# FOTA_LED_Indicators.net
KiCad netlist of a schematic drawn in Altium Designer
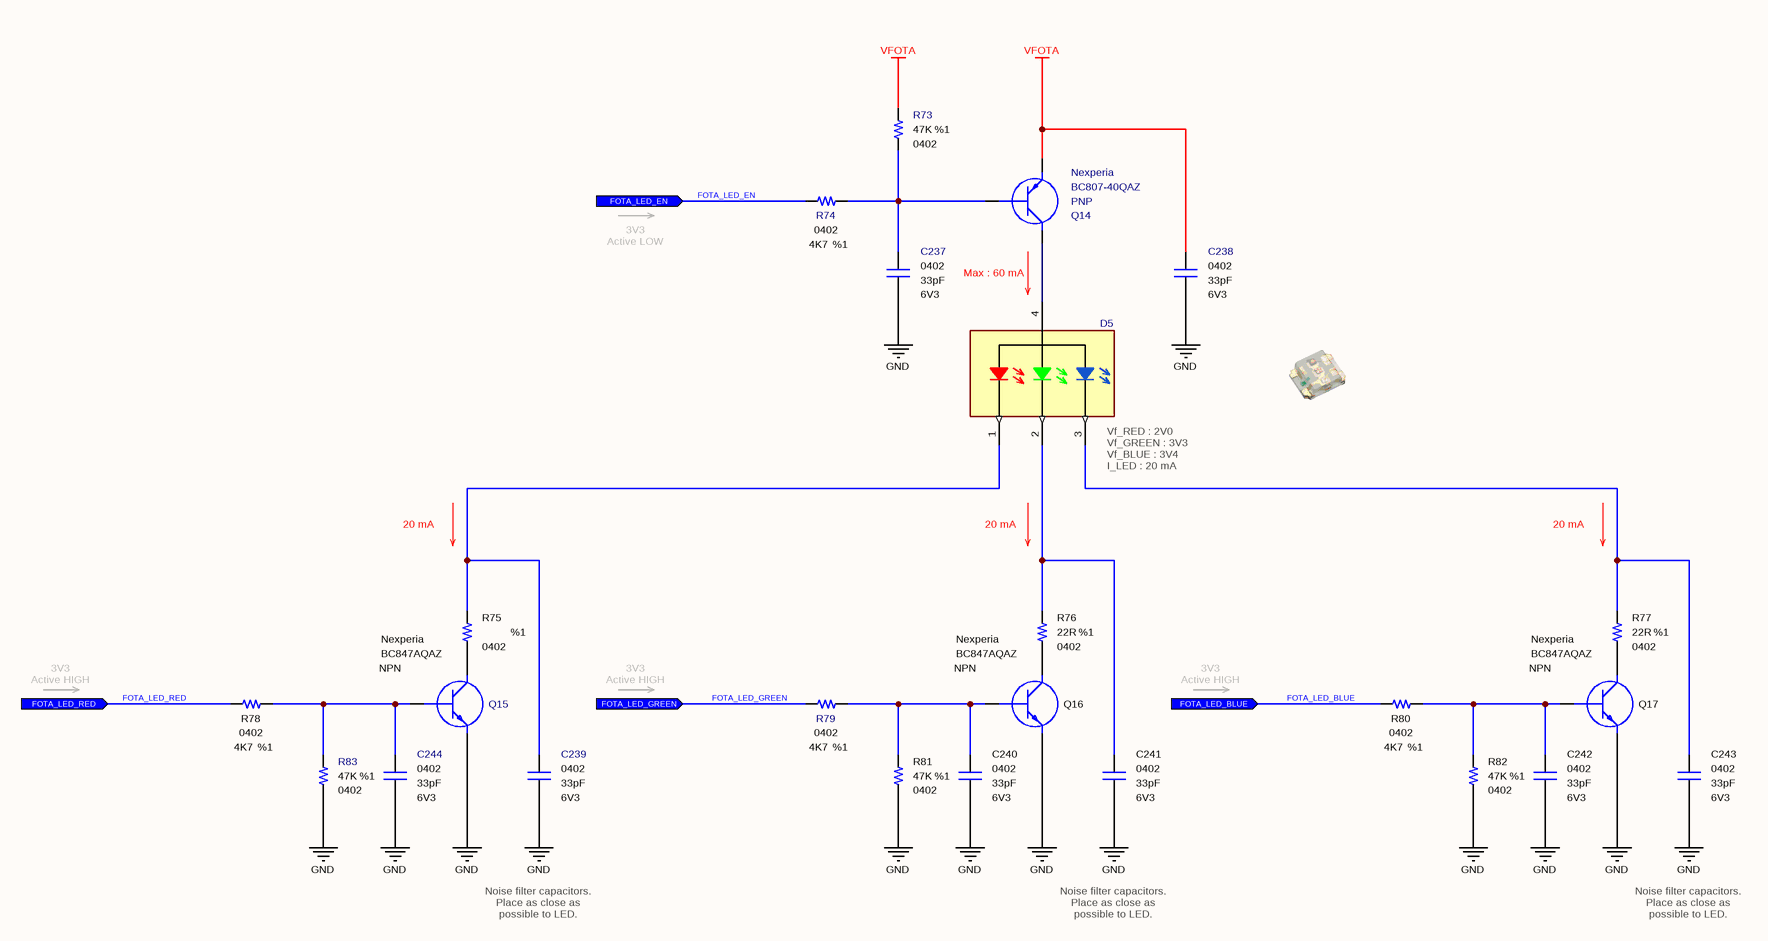
[diagram p0: FOTA LED Indicators.SchDoc]

(export (version "E")
  (design (tool "Eeschema 10.0.6"))
  (components
    (comp (ref "C237")
      (value "33pF")
      (footprint "CAPACITOR_0402")
      (description "Capacitor - 33pF [0402] (Ceramic)")
      (fields
        (field (name "CASE") "0402")
        (field (name "TOLERANCE") "10%")
        (field (name "VOLTAGE") "6V3")
        (field (name "MANUFACTURER PART NUMBER") "C0402C330J9RACAUTO")
      )
      (libsource (lib "Ovoo_Library") (part "Capacitor - 33pF [0402-6V3]"))
    )
    (comp (ref "C238")
      (value "33pF")
      (footprint "CAPACITOR_0402")
      (description "Capacitor - 33pF [0402] (Ceramic)")
      (fields
        (field (name "CASE") "0402")
        (field (name "TOLERANCE") "10%")
        (field (name "VOLTAGE") "6V3")
        (field (name "MANUFACTURER PART NUMBER") "C0402C330J9RACAUTO")
      )
      (libsource (lib "Ovoo_Library") (part "Capacitor - 33pF [0402-6V3]"))
    )
    (comp (ref "C239")
      (value "33pF")
      (footprint "CAPACITOR_0402")
      (description "Capacitor - 33pF [0402] (Ceramic)")
      (fields
        (field (name "CASE") "0402")
        (field (name "TOLERANCE") "10%")
        (field (name "VOLTAGE") "6V3")
        (field (name "MANUFACTURER PART NUMBER") "C0402C330J9RACAUTO")
      )
      (libsource (lib "Ovoo_Library") (part "Capacitor - 33pF [0402-6V3]"))
    )
    (comp (ref "C240")
      (value "33pF")
      (footprint "CAPACITOR_0402")
      (description "Capacitor - 33pF [0402] (Ceramic)")
      (fields
        (field (name "CASE") "0402")
        (field (name "TOLERANCE") "10%")
        (field (name "VOLTAGE") "6V3")
        (field (name "MANUFACTURER PART NUMBER") "C0402C330J9RACAUTO")
      )
      (libsource (lib "Ovoo_Library") (part "Capacitor - 33pF [0402-6V3]"))
    )
    (comp (ref "C241")
      (value "33pF")
      (footprint "CAPACITOR_0402")
      (description "Capacitor - 33pF [0402] (Ceramic)")
      (fields
        (field (name "CASE") "0402")
        (field (name "TOLERANCE") "10%")
        (field (name "VOLTAGE") "6V3")
        (field (name "MANUFACTURER PART NUMBER") "C0402C330J9RACAUTO")
      )
      (libsource (lib "Ovoo_Library") (part "Capacitor - 33pF [0402-6V3]"))
    )
    (comp (ref "C242")
      (value "33pF")
      (footprint "CAPACITOR_0402")
      (description "Capacitor - 33pF [0402] (Ceramic)")
      (fields
        (field (name "CASE") "0402")
        (field (name "TOLERANCE") "10%")
        (field (name "VOLTAGE") "6V3")
        (field (name "MANUFACTURER PART NUMBER") "C0402C330J9RACAUTO")
      )
      (libsource (lib "Ovoo_Library") (part "Capacitor - 33pF [0402-6V3]"))
    )
    (comp (ref "C243")
      (value "33pF")
      (footprint "CAPACITOR_0402")
      (description "Capacitor - 33pF [0402] (Ceramic)")
      (fields
        (field (name "CASE") "0402")
        (field (name "TOLERANCE") "10%")
        (field (name "VOLTAGE") "6V3")
        (field (name "MANUFACTURER PART NUMBER") "C0402C330J9RACAUTO")
      )
      (libsource (lib "Ovoo_Library") (part "Capacitor - 33pF [0402-6V3]"))
    )
    (comp (ref "C244")
      (value "33pF")
      (footprint "CAPACITOR_0402")
      (description "Capacitor - 33pF [0402] (Ceramic)")
      (fields
        (field (name "CASE") "0402")
        (field (name "TOLERANCE") "10%")
        (field (name "VOLTAGE") "6V3")
        (field (name "MANUFACTURER PART NUMBER") "C0402C330J9RACAUTO")
      )
      (libsource (lib "Ovoo_Library") (part "Capacitor - 33pF [0402-6V3]"))
    )
    (comp (ref "D5")
      (value "150066M153000")
      (footprint "Wurth_0606")
      (description "Standard LEDs - SMD PICOLED series Red LED")
      (fields (field (name "MOUSER PART NUMBER") "710-150066M153000"))
      (libsource (lib "Ovoo_Library") (part "Diode - RGB LED (150066M153000)"))
    )
    (comp (ref "Q14")
      (value "Bipolar PNP Transistors")
      (footprint "SOT1215")
      (description "Bipolar Transistors - BJT 45 V, 500 mA PNP gen purpose transistors")
      (fields
        (field (name "MOUSER PART NUMBER") "771-BC807-40QAZ")
        (field (name "POLARITY") "PNP")
        (field (name "MANUFACTURER NAME") "Nexperia")
        (field (name "MANUFACTURER PART NUMBER") "BC807-40QAZ")
      )
      (libsource (lib "Ovoo_Library") (part "Transistor - BC807"))
    )
    (comp (ref "Q15")
      (value "BC847AQAZ")
      (footprint "SOT1215")
      (description "Bipolar NPN Transistors")
      (fields
        (field (name "POLARITY") "NPN")
        (field (name "MANUFACTURER NAME") "Nexperia")
        (field (name "MANUFACTURER PART NUMBER") "BC847AQAZ")
      )
      (libsource (lib "Ovoo_Library") (part "Transistor - BC847"))
    )
    (comp (ref "Q16")
      (value "BC847AQAZ")
      (footprint "SOT1215")
      (description "Bipolar NPN Transistors")
      (fields
        (field (name "POLARITY") "NPN")
        (field (name "MANUFACTURER NAME") "Nexperia")
        (field (name "MANUFACTURER PART NUMBER") "BC847AQAZ")
      )
      (libsource (lib "Ovoo_Library") (part "Transistor - BC847"))
    )
    (comp (ref "Q17")
      (value "BC847AQAZ")
      (footprint "SOT1215")
      (description "Bipolar NPN Transistors")
      (fields
        (field (name "POLARITY") "NPN")
        (field (name "MANUFACTURER NAME") "Nexperia")
        (field (name "MANUFACTURER PART NUMBER") "BC847AQAZ")
      )
      (libsource (lib "Ovoo_Library") (part "Transistor - BC847"))
    )
    (comp (ref "R73")
      (value "47K")
      (footprint "RESISTOR_0402")
      (description "Thick Film Resistors - SMD 1/16 W 47 Kohms 1%")
      (fields
        (field (name "TOLERANCE") "%1")
        (field (name "CASE") "0402")
        (field (name "MANUFACTURER PART NUMBER") "CRCW040247K0FKED")
        (field (name "Comment") "47K - 0402 - %1 - 1/16W")
      )
      (libsource (lib "Ovoo_Library") (part "Resistor - 47K"))
    )
    (comp (ref "R74")
      (value "4K7")
      (footprint "RESISTOR_0402")
      (description "Thick Film Resistors - SMD 1/16 W 4.7 Kohms 1%")
      (fields
        (field (name "MANUFACTURER PART NUMBER") "CRCW04024K70FKED")
        (field (name "MOUSER PART NUMBER") "71-CRCW0402-4.7K-E3")
        (field (name "TOLERANCE") "%1")
        (field (name "CASE") "0402")
      )
      (libsource (lib "Ovoo_Library") (part "Resistor - 4K7"))
    )
    (comp (ref "R75")
      (value "Thick Film Resistor")
      (footprint "RESISTOR_0402")
      (description "Thick Film Resistors - SMD 1/16 W 64R9 Ohms 1%")
      (fields
        (field (name "MANUFACTURER PART NUMBER") "CRCW040264R9FKED")
        (field (name "MOUSER PART NUMBER") "71-CRCW0402-64.9-E3")
        (field (name "TOLERANCE") "%1")
        (field (name "CASE") "0402")
      )
      (libsource (lib "Ovoo_Library") (part "Resistor - 64R9"))
    )
    (comp (ref "R76")
      (value "22R")
      (footprint "RESISTOR_0402")
      (description "Thick Film Resistors - SMD 1/16 W 22R Ohms 1%")
      (fields
        (field (name "MANUFACTURER PART NUMBER") "CRCW040222R0FKED")
        (field (name "MOUSER PART NUMBER") "71-CRCW0402-22-E3")
        (field (name "TOLERANCE") "%1")
        (field (name "CASE") "0402")
      )
      (libsource (lib "Ovoo_Library") (part "Resistor - 22R"))
    )
    (comp (ref "R77")
      (value "22R")
      (footprint "RESISTOR_0402")
      (description "Thick Film Resistors - SMD 1/16 W 22R Ohms 1%")
      (fields
        (field (name "MANUFACTURER PART NUMBER") "CRCW040222R0FKED")
        (field (name "MOUSER PART NUMBER") "71-CRCW0402-22-E3")
        (field (name "TOLERANCE") "%1")
        (field (name "CASE") "0402")
      )
      (libsource (lib "Ovoo_Library") (part "Resistor - 22R"))
    )
    (comp (ref "R78")
      (value "4K7")
      (footprint "RESISTOR_0402")
      (description "Thick Film Resistors - SMD 1/16 W 4.7 Kohms 1%")
      (fields
        (field (name "MANUFACTURER PART NUMBER") "CRCW04024K70FKED")
        (field (name "MOUSER PART NUMBER") "71-CRCW0402-4.7K-E3")
        (field (name "TOLERANCE") "%1")
        (field (name "CASE") "0402")
      )
      (libsource (lib "Ovoo_Library") (part "Resistor - 4K7"))
    )
    (comp (ref "R79")
      (value "4K7")
      (footprint "RESISTOR_0402")
      (description "Thick Film Resistors - SMD 1/16 W 4.7 Kohms 1%")
      (fields
        (field (name "MANUFACTURER PART NUMBER") "CRCW04024K70FKED")
        (field (name "MOUSER PART NUMBER") "71-CRCW0402-4.7K-E3")
        (field (name "TOLERANCE") "%1")
        (field (name "CASE") "0402")
      )
      (libsource (lib "Ovoo_Library") (part "Resistor - 4K7"))
    )
    (comp (ref "R80")
      (value "4K7")
      (footprint "RESISTOR_0402")
      (description "Thick Film Resistors - SMD 1/16 W 4.7 Kohms 1%")
      (fields
        (field (name "MANUFACTURER PART NUMBER") "CRCW04024K70FKED")
        (field (name "MOUSER PART NUMBER") "71-CRCW0402-4.7K-E3")
        (field (name "TOLERANCE") "%1")
        (field (name "CASE") "0402")
      )
      (libsource (lib "Ovoo_Library") (part "Resistor - 4K7"))
    )
    (comp (ref "R81")
      (value "47K")
      (footprint "RESISTOR_0402")
      (description "Thick Film Resistors - SMD 1/16 W 47 Kohms 1%")
      (fields
        (field (name "TOLERANCE") "%1")
        (field (name "CASE") "0402")
        (field (name "MANUFACTURER PART NUMBER") "CRCW040247K0FKED")
        (field (name "Comment") "47K - 0402 - %1 - 1/16W")
      )
      (libsource (lib "Ovoo_Library") (part "Resistor - 47K"))
    )
    (comp (ref "R82")
      (value "47K")
      (footprint "RESISTOR_0402")
      (description "Thick Film Resistors - SMD 1/16 W 47 Kohms 1%")
      (fields
        (field (name "TOLERANCE") "%1")
        (field (name "CASE") "0402")
        (field (name "MANUFACTURER PART NUMBER") "CRCW040247K0FKED")
        (field (name "Comment") "47K - 0402 - %1 - 1/16W")
      )
      (libsource (lib "Ovoo_Library") (part "Resistor - 47K"))
    )
    (comp (ref "R83")
      (value "47K")
      (footprint "RESISTOR_0402")
      (description "Thick Film Resistors - SMD 1/16 W 47 Kohms 1%")
      (fields
        (field (name "TOLERANCE") "%1")
        (field (name "CASE") "0402")
        (field (name "MANUFACTURER PART NUMBER") "CRCW040247K0FKED")
        (field (name "Comment") "47K - 0402 - %1 - 1/16W")
      )
      (libsource (lib "Ovoo_Library") (part "Resistor - 47K"))
    )
  )
  (nets
    (net (code "1") (name "/FOTA_LED_BLUE") (class "Default")
      (node (ref "R80") (pin "2") (pinfunction "2_2") (pintype "passive"))
    )
    (net (code "2") (name "/FOTA_LED_EN") (class "Default")
      (node (ref "R74") (pin "2") (pinfunction "2_2") (pintype "passive"))
    )
    (net (code "3") (name "/FOTA_LED_GREEN") (class "Default")
      (node (ref "R79") (pin "2") (pinfunction "2_2") (pintype "passive"))
    )
    (net (code "4") (name "/FOTA_LED_RED") (class "Default")
      (node (ref "R78") (pin "2") (pinfunction "2_2") (pintype "passive"))
    )
    (net (code "5") (name "GND") (class "Default")
      (node (ref "C237") (pin "2") (pinfunction "2_2") (pintype "passive"))
      (node (ref "C238") (pin "2") (pinfunction "2_2") (pintype "passive"))
      (node (ref "C239") (pin "2") (pinfunction "2_2") (pintype "passive"))
      (node (ref "C240") (pin "2") (pinfunction "2_2") (pintype "passive"))
      (node (ref "C241") (pin "2") (pinfunction "2_2") (pintype "passive"))
      (node (ref "C242") (pin "2") (pinfunction "2_2") (pintype "passive"))
      (node (ref "C243") (pin "2") (pinfunction "2_2") (pintype "passive"))
      (node (ref "C244") (pin "2") (pinfunction "2_2") (pintype "passive"))
      (node (ref "Q15") (pin "2") (pinfunction "E_2") (pintype "passive"))
      (node (ref "Q16") (pin "2") (pinfunction "E_2") (pintype "passive"))
      (node (ref "Q17") (pin "2") (pinfunction "E_2") (pintype "passive"))
      (node (ref "R81") (pin "1") (pinfunction "1_1") (pintype "passive"))
      (node (ref "R82") (pin "1") (pinfunction "1_1") (pintype "passive"))
      (node (ref "R83") (pin "1") (pinfunction "1_1") (pintype "passive"))
    )
    (net (code "6") (name "Net-(C239-Pad1)") (class "Default")
      (node (ref "C239") (pin "1") (pinfunction "1_1") (pintype "passive"))
      (node (ref "D5") (pin "1") (pinfunction "1_1") (pintype "output"))
      (node (ref "R75") (pin "2") (pinfunction "2_2") (pintype "passive"))
    )
    (net (code "7") (name "Net-(C241-Pad1)") (class "Default")
      (node (ref "C241") (pin "1") (pinfunction "1_1") (pintype "passive"))
      (node (ref "D5") (pin "2") (pinfunction "2_2") (pintype "output"))
      (node (ref "R76") (pin "2") (pinfunction "2_2") (pintype "passive"))
    )
    (net (code "8") (name "Net-(C243-Pad1)") (class "Default")
      (node (ref "C243") (pin "1") (pinfunction "1_1") (pintype "passive"))
      (node (ref "D5") (pin "3") (pinfunction "3_3") (pintype "output"))
      (node (ref "R77") (pin "2") (pinfunction "2_2") (pintype "passive"))
    )
    (net (code "9") (name "Net-(Q14-B)") (class "Default")
      (node (ref "C237") (pin "1") (pinfunction "1_1") (pintype "passive"))
      (node (ref "Q14") (pin "1") (pinfunction "B_1") (pintype "passive"))
      (node (ref "R73") (pin "1") (pinfunction "1_1") (pintype "passive"))
      (node (ref "R74") (pin "1") (pinfunction "1_1") (pintype "passive"))
    )
    (net (code "10") (name "Net-(Q14-C)") (class "Default")
      (node (ref "D5") (pin "4") (pinfunction "4_4") (pintype "power_in"))
      (node (ref "Q14") (pin "3") (pinfunction "C_3") (pintype "passive"))
    )
    (net (code "11") (name "Net-(Q15-B)") (class "Default")
      (node (ref "C244") (pin "1") (pinfunction "1_1") (pintype "passive"))
      (node (ref "Q15") (pin "1") (pinfunction "B_1") (pintype "passive"))
      (node (ref "R78") (pin "1") (pinfunction "1_1") (pintype "passive"))
      (node (ref "R83") (pin "2") (pinfunction "2_2") (pintype "passive"))
    )
    (net (code "12") (name "Net-(Q15-C)") (class "Default")
      (node (ref "Q15") (pin "3") (pinfunction "C_3") (pintype "passive"))
      (node (ref "R75") (pin "1") (pinfunction "1_1") (pintype "passive"))
    )
    (net (code "13") (name "Net-(Q16-B)") (class "Default")
      (node (ref "C240") (pin "1") (pinfunction "1_1") (pintype "passive"))
      (node (ref "Q16") (pin "1") (pinfunction "B_1") (pintype "passive"))
      (node (ref "R79") (pin "1") (pinfunction "1_1") (pintype "passive"))
      (node (ref "R81") (pin "2") (pinfunction "2_2") (pintype "passive"))
    )
    (net (code "14") (name "Net-(Q16-C)") (class "Default")
      (node (ref "Q16") (pin "3") (pinfunction "C_3") (pintype "passive"))
      (node (ref "R76") (pin "1") (pinfunction "1_1") (pintype "passive"))
    )
    (net (code "15") (name "Net-(Q17-B)") (class "Default")
      (node (ref "C242") (pin "1") (pinfunction "1_1") (pintype "passive"))
      (node (ref "Q17") (pin "1") (pinfunction "B_1") (pintype "passive"))
      (node (ref "R80") (pin "1") (pinfunction "1_1") (pintype "passive"))
      (node (ref "R82") (pin "2") (pinfunction "2_2") (pintype "passive"))
    )
    (net (code "16") (name "Net-(Q17-C)") (class "Default")
      (node (ref "Q17") (pin "3") (pinfunction "C_3") (pintype "passive"))
      (node (ref "R77") (pin "1") (pinfunction "1_1") (pintype "passive"))
    )
    (net (code "17") (name "VFOTA") (class "Default")
      (node (ref "C238") (pin "1") (pinfunction "1_1") (pintype "passive"))
      (node (ref "Q14") (pin "2") (pinfunction "E_2") (pintype "passive"))
      (node (ref "R73") (pin "2") (pinfunction "2_2") (pintype "passive"))
    )
  )
)
